# sensorenhet.net
KiCad netlist of a schematic drawn in EAGLE
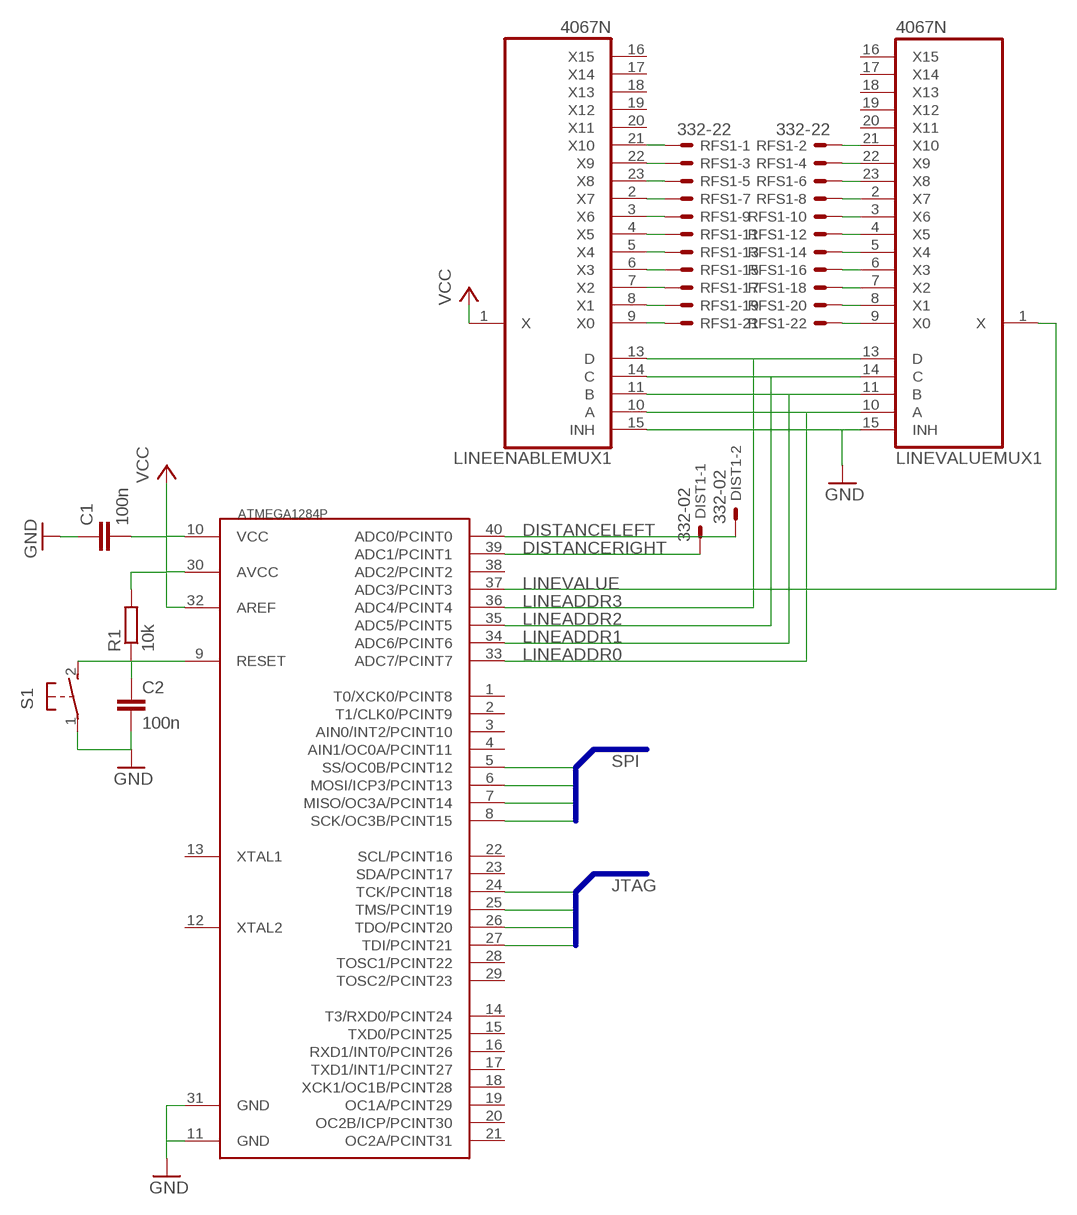
[diagram p0: schematic, sheet 1]

(export (version "E")
  (design (tool "Eeschema 10.0.6"))
  (components
    (comp (ref "ATMEGA1284P")
      (value "MEGA1284P")
      (footprint "eagle-import:DIL40")
      (libsource (lib "eagle-import") (part "MEGA1284P"))
    )
    (comp (ref "C1")
      (value "100n")
      (footprint "eagle-import:C1206")
      (libsource (lib "eagle-import") (part "C-EUC1206"))
    )
    (comp (ref "C2")
      (value "100n")
      (footprint "eagle-import:C1206")
      (libsource (lib "eagle-import") (part "C-EUC1206"))
    )
    (comp (ref "DIST1")
      (value "332-02")
      (footprint "eagle-import:332-02")
      (libsource (lib "eagle-import") (part "332-02"))
    )
    (comp (ref "LINEENABLEMUX1")
      (value "4067N")
      (footprint "eagle-import:DIL24-6")
      (libsource (lib "eagle-import") (part "4067N"))
    )
    (comp (ref "LINEVALUEMUX1")
      (value "4067N")
      (footprint "eagle-import:DIL24-6")
      (libsource (lib "eagle-import") (part "4067N"))
    )
    (comp (ref "R1")
      (value "10k")
      (footprint "eagle-import:V235_17")
      (libsource (lib "eagle-import") (part "R-EU_V235/17"))
    )
    (comp (ref "RFS1")
      (value "332-22")
      (footprint "eagle-import:332-22")
      (libsource (lib "eagle-import") (part "332-22"))
    )
    (comp (ref "S1")
      (value "31-XX")
      (footprint "eagle-import:B3F-31XX")
      (fields (field (name "MPN") "B3F-3100"))
      (libsource (lib "eagle-import") (part "31-XX"))
    )
  )
  (nets
    (net (code "3") (name "/DISTANCELEFT") (class "Default")
      (node (ref "ATMEGA1284P") (pin "40") (pinfunction "ADC0/PCINT0_40") (pintype "bidirectional"))
      (node (ref "DIST1") (pin "2") (pinfunction "S_2") (pintype "passive"))
    )
    (net (code "4") (name "/DISTANCERIGHT") (class "Default")
      (node (ref "ATMEGA1284P") (pin "39") (pinfunction "ADC1/PCINT1_39") (pintype "bidirectional"))
      (node (ref "DIST1") (pin "1") (pinfunction "S_1") (pintype "passive"))
    )
    (net (code "5") (name "/LINEADDR0") (class "Default")
      (node (ref "ATMEGA1284P") (pin "33") (pinfunction "ADC7/PCINT7_33") (pintype "bidirectional"))
      (node (ref "LINEENABLEMUX1") (pin "10") (pinfunction "A_10") (pintype "input"))
      (node (ref "LINEVALUEMUX1") (pin "10") (pinfunction "A_10") (pintype "input"))
    )
    (net (code "6") (name "/LINEADDR1") (class "Default")
      (node (ref "ATMEGA1284P") (pin "34") (pinfunction "ADC6/PCINT6_34") (pintype "bidirectional"))
      (node (ref "LINEENABLEMUX1") (pin "11") (pinfunction "B_11") (pintype "input"))
      (node (ref "LINEVALUEMUX1") (pin "11") (pinfunction "B_11") (pintype "input"))
    )
    (net (code "7") (name "/LINEADDR2") (class "Default")
      (node (ref "ATMEGA1284P") (pin "35") (pinfunction "ADC5/PCINT5_35") (pintype "bidirectional"))
      (node (ref "LINEENABLEMUX1") (pin "14") (pinfunction "C_14") (pintype "input"))
      (node (ref "LINEVALUEMUX1") (pin "14") (pinfunction "C_14") (pintype "input"))
    )
    (net (code "8") (name "/LINEADDR3") (class "Default")
      (node (ref "ATMEGA1284P") (pin "36") (pinfunction "ADC4/PCINT4_36") (pintype "bidirectional"))
      (node (ref "LINEENABLEMUX1") (pin "13") (pinfunction "D_13") (pintype "input"))
      (node (ref "LINEVALUEMUX1") (pin "13") (pinfunction "D_13") (pintype "input"))
    )
    (net (code "9") (name "/LINEVALUE") (class "Default")
      (node (ref "ATMEGA1284P") (pin "37") (pinfunction "ADC3/PCINT3_37") (pintype "bidirectional"))
      (node (ref "LINEVALUEMUX1") (pin "1") (pinfunction "X_1") (pintype "output"))
    )
    (net (code "12") (name "GND") (class "Default")
      (node (ref "ATMEGA1284P") (pin "11") (pinfunction "GND_11") (pintype "bidirectional"))
      (node (ref "ATMEGA1284P") (pin "31") (pinfunction "GND_31") (pintype "bidirectional"))
      (node (ref "C1") (pin "1") (pinfunction "1_1") (pintype "passive"))
      (node (ref "C2") (pin "2") (pinfunction "2_2") (pintype "passive"))
      (node (ref "LINEENABLEMUX1") (pin "15") (pinfunction "INH_15") (pintype "input"))
      (node (ref "LINEVALUEMUX1") (pin "15") (pinfunction "INH_15") (pintype "input"))
      (node (ref "S1") (pin "1") (pinfunction "P_1") (pintype "passive"))
    )
    (net (code "13") (name "Net-(ATMEGA1284P-RESET)") (class "Default")
      (node (ref "ATMEGA1284P") (pin "9") (pinfunction "RESET_9") (pintype "bidirectional"))
      (node (ref "C2") (pin "1") (pinfunction "1_1") (pintype "passive"))
      (node (ref "R1") (pin "1") (pinfunction "1_1") (pintype "passive"))
      (node (ref "S1") (pin "2") (pinfunction "S_2") (pintype "passive"))
    )
    (net (code "14") (name "Net-(LINEENABLEMUX1A-X0)") (class "Default")
      (node (ref "LINEENABLEMUX1") (pin "9") (pinfunction "X0_9") (pintype "input"))
      (node (ref "RFS1") (pin "21") (pinfunction "S_21") (pintype "passive"))
    )
    (net (code "15") (name "Net-(LINEENABLEMUX1A-X1)") (class "Default")
      (node (ref "LINEENABLEMUX1") (pin "8") (pinfunction "X1_8") (pintype "input"))
      (node (ref "RFS1") (pin "19") (pinfunction "S_19") (pintype "passive"))
    )
    (net (code "16") (name "Net-(LINEENABLEMUX1A-X2)") (class "Default")
      (node (ref "LINEENABLEMUX1") (pin "7") (pinfunction "X2_7") (pintype "input"))
      (node (ref "RFS1") (pin "17") (pinfunction "S_17") (pintype "passive"))
    )
    (net (code "17") (name "Net-(LINEENABLEMUX1A-X3)") (class "Default")
      (node (ref "LINEENABLEMUX1") (pin "6") (pinfunction "X3_6") (pintype "input"))
      (node (ref "RFS1") (pin "15") (pinfunction "S_15") (pintype "passive"))
    )
    (net (code "18") (name "Net-(LINEENABLEMUX1A-X4)") (class "Default")
      (node (ref "LINEENABLEMUX1") (pin "5") (pinfunction "X4_5") (pintype "input"))
      (node (ref "RFS1") (pin "13") (pinfunction "S_13") (pintype "passive"))
    )
    (net (code "19") (name "Net-(LINEENABLEMUX1A-X5)") (class "Default")
      (node (ref "LINEENABLEMUX1") (pin "4") (pinfunction "X5_4") (pintype "input"))
      (node (ref "RFS1") (pin "11") (pinfunction "S_11") (pintype "passive"))
    )
    (net (code "20") (name "Net-(LINEENABLEMUX1A-X6)") (class "Default")
      (node (ref "LINEENABLEMUX1") (pin "3") (pinfunction "X6_3") (pintype "input"))
      (node (ref "RFS1") (pin "9") (pinfunction "S_9") (pintype "passive"))
    )
    (net (code "21") (name "Net-(LINEENABLEMUX1A-X7)") (class "Default")
      (node (ref "LINEENABLEMUX1") (pin "2") (pinfunction "X7_2") (pintype "input"))
      (node (ref "RFS1") (pin "7") (pinfunction "S_7") (pintype "passive"))
    )
    (net (code "22") (name "Net-(LINEENABLEMUX1A-X8)") (class "Default")
      (node (ref "LINEENABLEMUX1") (pin "23") (pinfunction "X8_23") (pintype "input"))
      (node (ref "RFS1") (pin "5") (pinfunction "S_5") (pintype "passive"))
    )
    (net (code "23") (name "Net-(LINEENABLEMUX1A-X9)") (class "Default")
      (node (ref "LINEENABLEMUX1") (pin "22") (pinfunction "X9_22") (pintype "input"))
      (node (ref "RFS1") (pin "3") (pinfunction "S_3") (pintype "passive"))
    )
    (net (code "24") (name "Net-(LINEENABLEMUX1A-X10)") (class "Default")
      (node (ref "LINEENABLEMUX1") (pin "21") (pinfunction "X10_21") (pintype "input"))
      (node (ref "RFS1") (pin "1") (pinfunction "S_1") (pintype "passive"))
    )
    (net (code "25") (name "Net-(LINEVALUEMUX1A-X0)") (class "Default")
      (node (ref "LINEVALUEMUX1") (pin "9") (pinfunction "X0_9") (pintype "input"))
      (node (ref "RFS1") (pin "22") (pinfunction "S_22") (pintype "passive"))
    )
    (net (code "26") (name "Net-(LINEVALUEMUX1A-X1)") (class "Default")
      (node (ref "LINEVALUEMUX1") (pin "8") (pinfunction "X1_8") (pintype "input"))
      (node (ref "RFS1") (pin "20") (pinfunction "S_20") (pintype "passive"))
    )
    (net (code "27") (name "Net-(LINEVALUEMUX1A-X2)") (class "Default")
      (node (ref "LINEVALUEMUX1") (pin "7") (pinfunction "X2_7") (pintype "input"))
      (node (ref "RFS1") (pin "18") (pinfunction "S_18") (pintype "passive"))
    )
    (net (code "28") (name "Net-(LINEVALUEMUX1A-X3)") (class "Default")
      (node (ref "LINEVALUEMUX1") (pin "6") (pinfunction "X3_6") (pintype "input"))
      (node (ref "RFS1") (pin "16") (pinfunction "S_16") (pintype "passive"))
    )
    (net (code "29") (name "Net-(LINEVALUEMUX1A-X4)") (class "Default")
      (node (ref "LINEVALUEMUX1") (pin "5") (pinfunction "X4_5") (pintype "input"))
      (node (ref "RFS1") (pin "14") (pinfunction "S_14") (pintype "passive"))
    )
    (net (code "30") (name "Net-(LINEVALUEMUX1A-X5)") (class "Default")
      (node (ref "LINEVALUEMUX1") (pin "4") (pinfunction "X5_4") (pintype "input"))
      (node (ref "RFS1") (pin "12") (pinfunction "S_12") (pintype "passive"))
    )
    (net (code "31") (name "Net-(LINEVALUEMUX1A-X6)") (class "Default")
      (node (ref "LINEVALUEMUX1") (pin "3") (pinfunction "X6_3") (pintype "input"))
      (node (ref "RFS1") (pin "10") (pinfunction "S_10") (pintype "passive"))
    )
    (net (code "32") (name "Net-(LINEVALUEMUX1A-X7)") (class "Default")
      (node (ref "LINEVALUEMUX1") (pin "2") (pinfunction "X7_2") (pintype "input"))
      (node (ref "RFS1") (pin "8") (pinfunction "S_8") (pintype "passive"))
    )
    (net (code "33") (name "Net-(LINEVALUEMUX1A-X8)") (class "Default")
      (node (ref "LINEVALUEMUX1") (pin "23") (pinfunction "X8_23") (pintype "input"))
      (node (ref "RFS1") (pin "6") (pinfunction "S_6") (pintype "passive"))
    )
    (net (code "34") (name "Net-(LINEVALUEMUX1A-X9)") (class "Default")
      (node (ref "LINEVALUEMUX1") (pin "22") (pinfunction "X9_22") (pintype "input"))
      (node (ref "RFS1") (pin "4") (pinfunction "S_4") (pintype "passive"))
    )
    (net (code "35") (name "Net-(LINEVALUEMUX1A-X10)") (class "Default")
      (node (ref "LINEVALUEMUX1") (pin "21") (pinfunction "X10_21") (pintype "input"))
      (node (ref "RFS1") (pin "2") (pinfunction "S_2") (pintype "passive"))
    )
    (net (code "36") (name "VCC") (class "Default")
      (node (ref "ATMEGA1284P") (pin "10") (pinfunction "VCC_10") (pintype "bidirectional"))
      (node (ref "ATMEGA1284P") (pin "30") (pinfunction "AVCC_30") (pintype "bidirectional"))
      (node (ref "ATMEGA1284P") (pin "32") (pinfunction "AREF_32") (pintype "bidirectional"))
      (node (ref "C1") (pin "2") (pinfunction "2_2") (pintype "passive"))
      (node (ref "LINEENABLEMUX1") (pin "1") (pinfunction "X_1") (pintype "output"))
      (node (ref "R1") (pin "2") (pinfunction "2_2") (pintype "passive"))
    )
    (net (code "37") (name "unconnected-(ATMEGA1284P-ADC2{slash}PCINT2-Pad38)") (class "Default")
      (node (ref "ATMEGA1284P") (pin "38") (pinfunction "ADC2/PCINT2_38") (pintype "bidirectional"))
    )
    (net (code "38") (name "unconnected-(ATMEGA1284P-AIN0{slash}INT2{slash}PCINT10-Pad3)") (class "Default")
      (node (ref "ATMEGA1284P") (pin "3") (pinfunction "AIN0/INT2/PCINT10_3") (pintype "bidirectional"))
    )
    (net (code "39") (name "unconnected-(ATMEGA1284P-AIN1{slash}OC0A{slash}PCINT11-Pad4)") (class "Default")
      (node (ref "ATMEGA1284P") (pin "4") (pinfunction "AIN1/OC0A/PCINT11_4") (pintype "bidirectional"))
    )
    (net (code "40") (name "unconnected-(ATMEGA1284P-MISO{slash}OC3A{slash}PCINT14-Pad7)") (class "Default")
      (node (ref "ATMEGA1284P") (pin "7") (pinfunction "MISO/OC3A/PCINT14_7") (pintype "bidirectional"))
    )
    (net (code "41") (name "unconnected-(ATMEGA1284P-MOSI{slash}ICP3{slash}PCINT13-Pad6)") (class "Default")
      (node (ref "ATMEGA1284P") (pin "6") (pinfunction "MOSI/ICP3/PCINT13_6") (pintype "bidirectional"))
    )
    (net (code "42") (name "unconnected-(ATMEGA1284P-OC1A{slash}PCINT29-Pad19)") (class "Default")
      (node (ref "ATMEGA1284P") (pin "19") (pinfunction "OC1A/PCINT29_19") (pintype "bidirectional"))
    )
    (net (code "43") (name "unconnected-(ATMEGA1284P-OC2A{slash}PCINT31-Pad21)") (class "Default")
      (node (ref "ATMEGA1284P") (pin "21") (pinfunction "OC2A/PCINT31_21") (pintype "bidirectional"))
    )
    (net (code "44") (name "unconnected-(ATMEGA1284P-OC2B{slash}ICP{slash}PCINT30-Pad20)") (class "Default")
      (node (ref "ATMEGA1284P") (pin "20") (pinfunction "OC2B/ICP/PCINT30_20") (pintype "bidirectional"))
    )
    (net (code "45") (name "unconnected-(ATMEGA1284P-RXD1{slash}INT0{slash}PCINT26-Pad16)") (class "Default")
      (node (ref "ATMEGA1284P") (pin "16") (pinfunction "RXD1/INT0/PCINT26_16") (pintype "bidirectional"))
    )
    (net (code "46") (name "unconnected-(ATMEGA1284P-SCK{slash}OC3B{slash}PCINT15-Pad8)") (class "Default")
      (node (ref "ATMEGA1284P") (pin "8") (pinfunction "SCK/OC3B/PCINT15_8") (pintype "bidirectional"))
    )
    (net (code "47") (name "unconnected-(ATMEGA1284P-SCL{slash}PCINT16-Pad22)") (class "Default")
      (node (ref "ATMEGA1284P") (pin "22") (pinfunction "SCL/PCINT16_22") (pintype "bidirectional"))
    )
    (net (code "48") (name "unconnected-(ATMEGA1284P-SDA{slash}PCINT17-Pad23)") (class "Default")
      (node (ref "ATMEGA1284P") (pin "23") (pinfunction "SDA/PCINT17_23") (pintype "bidirectional"))
    )
    (net (code "49") (name "unconnected-(ATMEGA1284P-SS{slash}OC0B{slash}PCINT12-Pad5)") (class "Default")
      (node (ref "ATMEGA1284P") (pin "5") (pinfunction "SS/OC0B/PCINT12_5") (pintype "bidirectional"))
    )
    (net (code "50") (name "unconnected-(ATMEGA1284P-T0{slash}XCK0{slash}PCINT8-Pad1)") (class "Default")
      (node (ref "ATMEGA1284P") (pin "1") (pinfunction "T0/XCK0/PCINT8_1") (pintype "bidirectional"))
    )
    (net (code "51") (name "unconnected-(ATMEGA1284P-T1{slash}CLK0{slash}PCINT9-Pad2)") (class "Default")
      (node (ref "ATMEGA1284P") (pin "2") (pinfunction "T1/CLK0/PCINT9_2") (pintype "bidirectional"))
    )
    (net (code "52") (name "unconnected-(ATMEGA1284P-T3{slash}RXD0{slash}PCINT24-Pad14)") (class "Default")
      (node (ref "ATMEGA1284P") (pin "14") (pinfunction "T3/RXD0/PCINT24_14") (pintype "bidirectional"))
    )
    (net (code "53") (name "unconnected-(ATMEGA1284P-TCK{slash}PCINT18-Pad24)") (class "Default")
      (node (ref "ATMEGA1284P") (pin "24") (pinfunction "TCK/PCINT18_24") (pintype "bidirectional"))
    )
    (net (code "54") (name "unconnected-(ATMEGA1284P-TDI{slash}PCINT21-Pad27)") (class "Default")
      (node (ref "ATMEGA1284P") (pin "27") (pinfunction "TDI/PCINT21_27") (pintype "bidirectional"))
    )
    (net (code "55") (name "unconnected-(ATMEGA1284P-TDO{slash}PCINT20-Pad26)") (class "Default")
      (node (ref "ATMEGA1284P") (pin "26") (pinfunction "TDO/PCINT20_26") (pintype "bidirectional"))
    )
    (net (code "56") (name "unconnected-(ATMEGA1284P-TMS{slash}PCINT19-Pad25)") (class "Default")
      (node (ref "ATMEGA1284P") (pin "25") (pinfunction "TMS/PCINT19_25") (pintype "bidirectional"))
    )
    (net (code "57") (name "unconnected-(ATMEGA1284P-TOSC1{slash}PCINT22-Pad28)") (class "Default")
      (node (ref "ATMEGA1284P") (pin "28") (pinfunction "TOSC1/PCINT22_28") (pintype "bidirectional"))
    )
    (net (code "58") (name "unconnected-(ATMEGA1284P-TOSC2{slash}PCINT23-Pad29)") (class "Default")
      (node (ref "ATMEGA1284P") (pin "29") (pinfunction "TOSC2/PCINT23_29") (pintype "bidirectional"))
    )
    (net (code "59") (name "unconnected-(ATMEGA1284P-TXD0{slash}PCINT25-Pad15)") (class "Default")
      (node (ref "ATMEGA1284P") (pin "15") (pinfunction "TXD0/PCINT25_15") (pintype "bidirectional"))
    )
    (net (code "60") (name "unconnected-(ATMEGA1284P-TXD1{slash}INT1{slash}PCINT27-Pad17)") (class "Default")
      (node (ref "ATMEGA1284P") (pin "17") (pinfunction "TXD1/INT1/PCINT27_17") (pintype "bidirectional"))
    )
    (net (code "61") (name "unconnected-(ATMEGA1284P-XCK1{slash}OC1B{slash}PCINT28-Pad18)") (class "Default")
      (node (ref "ATMEGA1284P") (pin "18") (pinfunction "XCK1/OC1B/PCINT28_18") (pintype "bidirectional"))
    )
    (net (code "62") (name "unconnected-(ATMEGA1284P-XTAL1-Pad13)") (class "Default")
      (node (ref "ATMEGA1284P") (pin "13") (pinfunction "XTAL1_13") (pintype "bidirectional"))
    )
    (net (code "63") (name "unconnected-(ATMEGA1284P-XTAL2-Pad12)") (class "Default")
      (node (ref "ATMEGA1284P") (pin "12") (pinfunction "XTAL2_12") (pintype "bidirectional"))
    )
    (net (code "64") (name "unconnected-(LINEENABLEMUX1A-X11-Pad20)") (class "Default")
      (node (ref "LINEENABLEMUX1") (pin "20") (pinfunction "X11_20") (pintype "input"))
    )
    (net (code "65") (name "unconnected-(LINEENABLEMUX1A-X12-Pad19)") (class "Default")
      (node (ref "LINEENABLEMUX1") (pin "19") (pinfunction "X12_19") (pintype "input"))
    )
    (net (code "66") (name "unconnected-(LINEENABLEMUX1A-X13-Pad18)") (class "Default")
      (node (ref "LINEENABLEMUX1") (pin "18") (pinfunction "X13_18") (pintype "input"))
    )
    (net (code "67") (name "unconnected-(LINEENABLEMUX1A-X14-Pad17)") (class "Default")
      (node (ref "LINEENABLEMUX1") (pin "17") (pinfunction "X14_17") (pintype "input"))
    )
    (net (code "68") (name "unconnected-(LINEENABLEMUX1A-X15-Pad16)") (class "Default")
      (node (ref "LINEENABLEMUX1") (pin "16") (pinfunction "X15_16") (pintype "input"))
    )
    (net (code "69") (name "unconnected-(LINEVALUEMUX1A-X11-Pad20)") (class "Default")
      (node (ref "LINEVALUEMUX1") (pin "20") (pinfunction "X11_20") (pintype "input"))
    )
    (net (code "70") (name "unconnected-(LINEVALUEMUX1A-X12-Pad19)") (class "Default")
      (node (ref "LINEVALUEMUX1") (pin "19") (pinfunction "X12_19") (pintype "input"))
    )
    (net (code "71") (name "unconnected-(LINEVALUEMUX1A-X13-Pad18)") (class "Default")
      (node (ref "LINEVALUEMUX1") (pin "18") (pinfunction "X13_18") (pintype "input"))
    )
    (net (code "72") (name "unconnected-(LINEVALUEMUX1A-X14-Pad17)") (class "Default")
      (node (ref "LINEVALUEMUX1") (pin "17") (pinfunction "X14_17") (pintype "input"))
    )
    (net (code "73") (name "unconnected-(LINEVALUEMUX1A-X15-Pad16)") (class "Default")
      (node (ref "LINEVALUEMUX1") (pin "16") (pinfunction "X15_16") (pintype "input"))
    )
  )
)
